# BMS_Rev3_logic.net
KiCad netlist of a schematic drawn in EAGLE
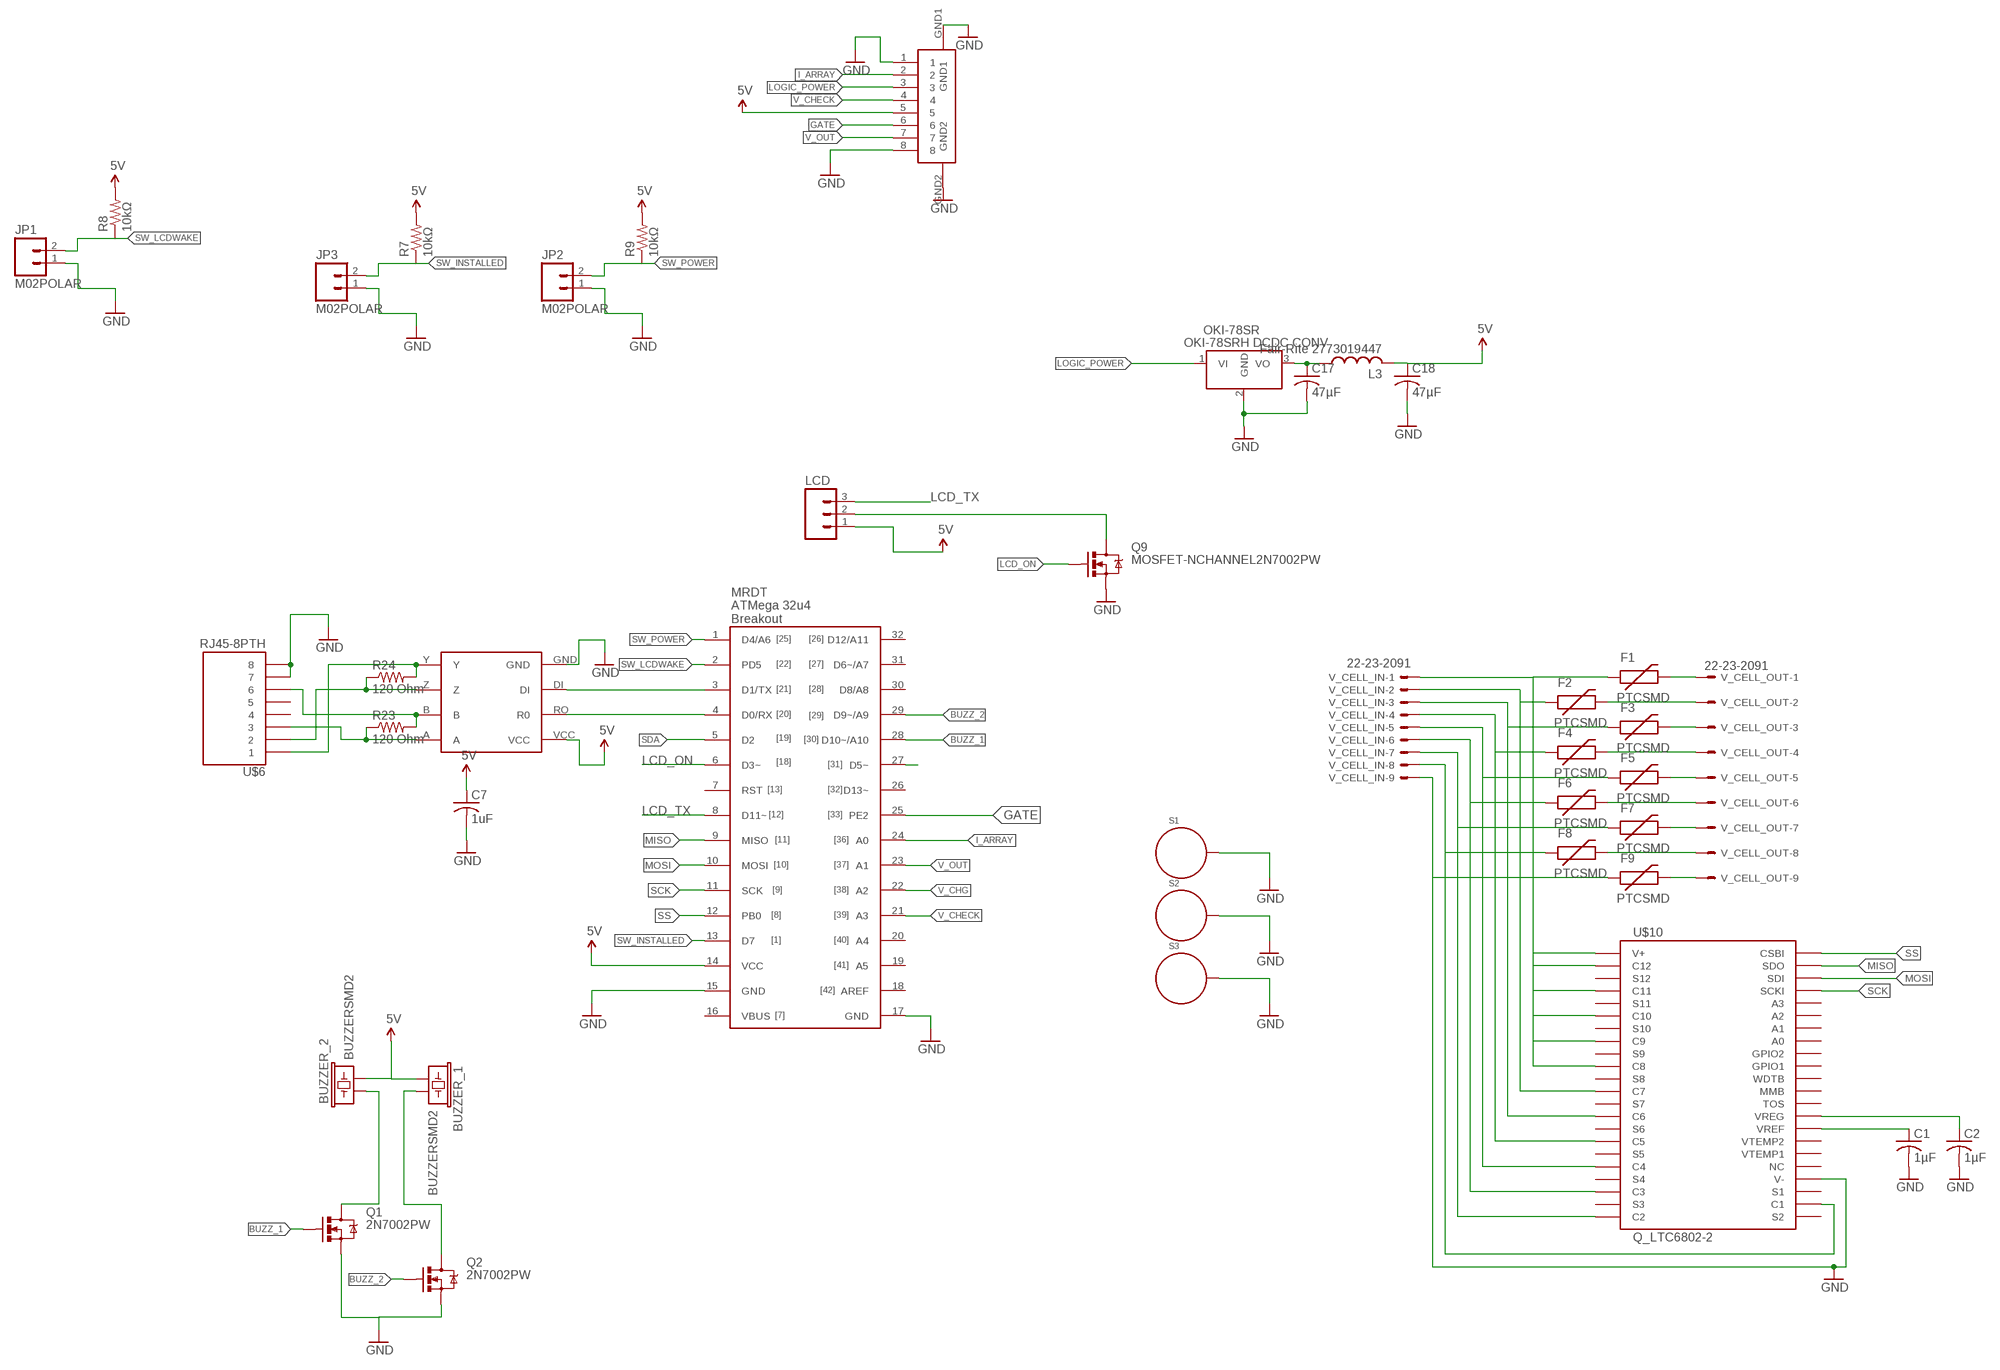
[diagram p0: schematic, sheet 1]

(export (version "E")
  (design (tool "Eeschema 10.0.6"))
  (components
    (comp (ref "BUZZER_1")
      (value "BUZZERSMD2")
      (footprint "eagle-import:BUZZER-CCV")
      (libsource (lib "eagle-import") (part "BUZZERSMD2"))
    )
    (comp (ref "BUZZER_2")
      (value "BUZZERSMD2")
      (footprint "eagle-import:BUZZER-CCV")
      (libsource (lib "eagle-import") (part "BUZZERSMD2"))
    )
    (comp (ref "C1")
      (value "1µF")
      (footprint "eagle-import:C1206")
      (libsource (lib "eagle-import") (part "C-USC1206"))
    )
    (comp (ref "C2")
      (value "1µF")
      (footprint "eagle-import:C1206")
      (libsource (lib "eagle-import") (part "C-USC1206"))
    )
    (comp (ref "C7")
      (value "1uF")
      (footprint "eagle-import:C1206")
      (libsource (lib "eagle-import") (part "C-USC1206"))
    )
    (comp (ref "C17")
      (value "47µF")
      (footprint "eagle-import:C1206")
      (libsource (lib "eagle-import") (part "C-USC1206"))
    )
    (comp (ref "C18")
      (value "47µF")
      (footprint "eagle-import:C1206")
      (libsource (lib "eagle-import") (part "C-USC1206"))
    )
    (comp (ref "F1")
      (value "PTCSMD")
      (footprint "eagle-import:PTC-1206")
      (libsource (lib "eagle-import") (part "PTCSMD"))
    )
    (comp (ref "F2")
      (value "PTCSMD")
      (footprint "eagle-import:PTC-1206")
      (libsource (lib "eagle-import") (part "PTCSMD"))
    )
    (comp (ref "F3")
      (value "PTCSMD")
      (footprint "eagle-import:PTC-1206")
      (libsource (lib "eagle-import") (part "PTCSMD"))
    )
    (comp (ref "F4")
      (value "PTCSMD")
      (footprint "eagle-import:PTC-1206")
      (libsource (lib "eagle-import") (part "PTCSMD"))
    )
    (comp (ref "F5")
      (value "PTCSMD")
      (footprint "eagle-import:PTC-1206")
      (libsource (lib "eagle-import") (part "PTCSMD"))
    )
    (comp (ref "F6")
      (value "PTCSMD")
      (footprint "eagle-import:PTC-1206")
      (libsource (lib "eagle-import") (part "PTCSMD"))
    )
    (comp (ref "F7")
      (value "PTCSMD")
      (footprint "eagle-import:PTC-1206")
      (libsource (lib "eagle-import") (part "PTCSMD"))
    )
    (comp (ref "F8")
      (value "PTCSMD")
      (footprint "eagle-import:PTC-1206")
      (libsource (lib "eagle-import") (part "PTCSMD"))
    )
    (comp (ref "F9")
      (value "PTCSMD")
      (footprint "eagle-import:PTC-1206")
      (libsource (lib "eagle-import") (part "PTCSMD"))
    )
    (comp (ref "JP1")
      (value "M02POLAR")
      (footprint "eagle-import:MOLEX-1X2")
      (libsource (lib "eagle-import") (part "M02POLAR"))
    )
    (comp (ref "JP2")
      (value "M02POLAR")
      (footprint "eagle-import:MOLEX-1X2")
      (libsource (lib "eagle-import") (part "M02POLAR"))
    )
    (comp (ref "JP3")
      (value "M02POLAR")
      (footprint "eagle-import:MOLEX-1X2")
      (libsource (lib "eagle-import") (part "M02POLAR"))
    )
    (comp (ref "L3")
      (value "Fair-Rite 2773019447")
      (footprint "eagle-import:L8530M")
      (libsource (lib "eagle-import") (part "L-USL8530M"))
    )
    (comp (ref "LCD")
      (value "M03POLAR")
      (footprint "eagle-import:MOLEX-1X3")
      (libsource (lib "eagle-import") (part "M03POLAR"))
    )
    (comp (ref "OKI-78SR")
      (value "Q_OKI-78SR")
      (footprint "eagle-import:OKI-78SRH")
      (libsource (lib "eagle-import") (part "Q_OKI-78SR"))
    )
    (comp (ref "Q1")
      (value "2N7002PW")
      (footprint "eagle-import:SOT323")
      (libsource (lib "eagle-import") (part "MOSFET-NCHANNEL2N7002PW"))
    )
    (comp (ref "Q2")
      (value "2N7002PW")
      (footprint "eagle-import:SOT323")
      (libsource (lib "eagle-import") (part "MOSFET-NCHANNEL2N7002PW"))
    )
    (comp (ref "Q9")
      (value "MOSFET-NCHANNEL2N7002PW")
      (footprint "eagle-import:SOT323")
      (libsource (lib "eagle-import") (part "MOSFET-NCHANNEL2N7002PW"))
    )
    (comp (ref "R7")
      (value "10kΩ")
      (footprint "eagle-import:R1206")
      (libsource (lib "eagle-import") (part "R-US_R1206"))
    )
    (comp (ref "R8")
      (value "10kΩ")
      (footprint "eagle-import:R1206")
      (libsource (lib "eagle-import") (part "R-US_R1206"))
    )
    (comp (ref "R9")
      (value "10kΩ")
      (footprint "eagle-import:R1206")
      (libsource (lib "eagle-import") (part "R-US_R1206"))
    )
    (comp (ref "R23")
      (value "120 Ohm")
      (footprint "eagle-import:1206")
      (libsource (lib "eagle-import") (part "RESISTOR1206"))
    )
    (comp (ref "R24")
      (value "120 Ohm")
      (footprint "eagle-import:1206")
      (libsource (lib "eagle-import") (part "RESISTOR1206"))
    )
    (comp (ref "S1")
      (value "STANDOFF_ELECTRICAL")
      (footprint "eagle-import:STANDOFF-ELECTRICAL")
      (libsource (lib "eagle-import") (part "STANDOFF_ELECTRICAL"))
    )
    (comp (ref "S2")
      (value "STANDOFF_ELECTRICAL")
      (footprint "eagle-import:STANDOFF-ELECTRICAL")
      (libsource (lib "eagle-import") (part "STANDOFF_ELECTRICAL"))
    )
    (comp (ref "S3")
      (value "STANDOFF_ELECTRICAL")
      (footprint "eagle-import:STANDOFF-ELECTRICAL")
      (libsource (lib "eagle-import") (part "STANDOFF_ELECTRICAL"))
    )
    (comp (ref "U$1")
      (value "8POS_LOGIC")
      (footprint "eagle-import:LOGIC_CONNECT")
      (libsource (lib "eagle-import") (part "8POS_LOGIC"))
    )
    (comp (ref "U$3")
      (value "32U4_BREAKOUT")
      (footprint "eagle-import:32U4_MCU_DIP")
      (libsource (lib "eagle-import") (part "32U4_BREAKOUT"))
    )
    (comp (ref "U$6")
      (value "RJ45-8PTH")
      (footprint "eagle-import:RJ45-8")
      (libsource (lib "eagle-import") (part "RJ45-8PTH"))
    )
    (comp (ref "U$9")
      (value "MAX3077")
      (footprint "eagle-import:MAX3070E")
      (libsource (lib "eagle-import") (part "MAX3077"))
    )
    (comp (ref "U$10")
      (value "Q_LTC6802-2")
      (footprint "eagle-import:SSOP44")
      (libsource (lib "eagle-import") (part "Q_LTC6802-2"))
    )
    (comp (ref "V_CELL_IN")
      (value "22-23-2091")
      (footprint "eagle-import:22-23-2091")
      (fields (field (name "MF") "MOLEX"))
      (libsource (lib "eagle-import") (part "22-23-2091"))
    )
    (comp (ref "V_CELL_OUT")
      (value "22-23-2091")
      (footprint "eagle-import:22-23-2091")
      (fields (field (name "MF") "MOLEX"))
      (libsource (lib "eagle-import") (part "22-23-2091"))
    )
  )
  (nets
    (net (code "1") (name "/LCD_TX") (class "Default")
      (node (ref "LCD") (pin "3") (pinfunction "3_3") (pintype "passive"))
      (node (ref "U$3") (pin "8") (pinfunction "D11~{}_8") (pintype "bidirectional"))
    )
    (net (code "2") (name "5V") (class "Default")
      (node (ref "BUZZER_1") (pin "+") (pinfunction "1_+") (pintype "passive"))
      (node (ref "BUZZER_2") (pin "-") (pinfunction "2_-") (pintype "passive"))
      (node (ref "C18") (pin "1") (pinfunction "1_1") (pintype "passive"))
      (node (ref "C7") (pin "1") (pinfunction "1_1") (pintype "passive"))
      (node (ref "L3") (pin "2") (pinfunction "2_2") (pintype "passive"))
      (node (ref "LCD") (pin "1") (pinfunction "1_1") (pintype "passive"))
      (node (ref "R7") (pin "2") (pinfunction "2_2") (pintype "passive"))
      (node (ref "R8") (pin "2") (pinfunction "2_2") (pintype "passive"))
      (node (ref "R9") (pin "2") (pinfunction "2_2") (pintype "passive"))
      (node (ref "U$1") (pin "5") (pinfunction "5_5") (pintype "bidirectional"))
      (node (ref "U$3") (pin "14") (pinfunction "VCC_14") (pintype "bidirectional"))
      (node (ref "U$9") (pin "VCC") (pinfunction "VCC_VCC") (pintype "bidirectional"))
    )
    (net (code "3") (name "BUZZ_1") (class "Default")
      (node (ref "Q1") (pin "1") (pinfunction "G_1") (pintype "passive"))
      (node (ref "U$3") (pin "28") (pinfunction "D10~{/A10}_28") (pintype "bidirectional"))
    )
    (net (code "4") (name "BUZZ_2") (class "Default")
      (node (ref "Q2") (pin "1") (pinfunction "G_1") (pintype "passive"))
      (node (ref "U$3") (pin "29") (pinfunction "D9~{/A9}_29") (pintype "bidirectional"))
    )
    (net (code "5") (name "GATE") (class "Default")
      (node (ref "U$1") (pin "6") (pinfunction "6_6") (pintype "bidirectional"))
      (node (ref "U$3") (pin "25") (pinfunction "PE2_25") (pintype "bidirectional"))
    )
    (net (code "6") (name "GND") (class "Default")
      (node (ref "C1") (pin "2") (pinfunction "2_2") (pintype "passive"))
      (node (ref "C17") (pin "2") (pinfunction "2_2") (pintype "passive"))
      (node (ref "C18") (pin "2") (pinfunction "2_2") (pintype "passive"))
      (node (ref "C2") (pin "2") (pinfunction "2_2") (pintype "passive"))
      (node (ref "C7") (pin "2") (pinfunction "2_2") (pintype "passive"))
      (node (ref "F9") (pin "1") (pinfunction "1_1") (pintype "bidirectional"))
      (node (ref "JP1") (pin "1") (pinfunction "1_1") (pintype "passive"))
      (node (ref "JP2") (pin "1") (pinfunction "1_1") (pintype "passive"))
      (node (ref "JP3") (pin "1") (pinfunction "1_1") (pintype "passive"))
      (node (ref "OKI-78SR") (pin "2") (pinfunction "GND_2") (pintype "bidirectional"))
      (node (ref "Q1") (pin "2") (pinfunction "S_2") (pintype "passive"))
      (node (ref "Q2") (pin "2") (pinfunction "S_2") (pintype "passive"))
      (node (ref "Q9") (pin "2") (pinfunction "S_2") (pintype "passive"))
      (node (ref "S1") (pin "P1") (pinfunction "P$1_P1") (pintype "bidirectional"))
      (node (ref "S2") (pin "P1") (pinfunction "P$1_P1") (pintype "bidirectional"))
      (node (ref "S3") (pin "P1") (pinfunction "P$1_P1") (pintype "bidirectional"))
      (node (ref "U$1") (pin "1") (pinfunction "1_1") (pintype "bidirectional"))
      (node (ref "U$1") (pin "8") (pinfunction "8_8") (pintype "bidirectional"))
      (node (ref "U$1") (pin "GND1") (pinfunction "GND1_GND1") (pintype "bidirectional"))
      (node (ref "U$1") (pin "GND2") (pinfunction "GND2_GND2") (pintype "bidirectional"))
      (node (ref "U$10") (pin "26") (pinfunction "V-_26") (pintype "bidirectional"))
      (node (ref "U$3") (pin "15") (pinfunction "GND_15") (pintype "bidirectional"))
      (node (ref "U$3") (pin "17") (pinfunction "GND_17") (pintype "bidirectional"))
      (node (ref "U$6") (pin "7") (pinfunction "7_7") (pintype "bidirectional"))
      (node (ref "U$6") (pin "8") (pinfunction "8_8") (pintype "bidirectional"))
      (node (ref "U$9") (pin "GND") (pinfunction "GND_GND") (pintype "bidirectional"))
      (node (ref "V_CELL_IN") (pin "9") (pinfunction "S_9") (pintype "passive"))
    )
    (net (code "7") (name "I_ARRAY") (class "Default")
      (node (ref "U$1") (pin "2") (pinfunction "2_2") (pintype "bidirectional"))
      (node (ref "U$3") (pin "24") (pinfunction "A0_24") (pintype "bidirectional"))
    )
    (net (code "8") (name "LCD_ON") (class "Default")
      (node (ref "Q9") (pin "1") (pinfunction "G_1") (pintype "passive"))
      (node (ref "U$3") (pin "6") (pinfunction "D3~{}_6") (pintype "bidirectional"))
    )
    (net (code "9") (name "LOGIC_POWER") (class "Default")
      (node (ref "OKI-78SR") (pin "1") (pinfunction "VI_1") (pintype "bidirectional"))
      (node (ref "U$1") (pin "3") (pinfunction "3_3") (pintype "bidirectional"))
    )
    (net (code "10") (name "MISO") (class "Default")
      (node (ref "U$10") (pin "43") (pinfunction "SDO_43") (pintype "bidirectional"))
      (node (ref "U$3") (pin "9") (pinfunction "MISO_9") (pintype "bidirectional"))
    )
    (net (code "11") (name "MOSI") (class "Default")
      (node (ref "U$10") (pin "42") (pinfunction "SDI_42") (pintype "bidirectional"))
      (node (ref "U$3") (pin "10") (pinfunction "MOSI_10") (pintype "bidirectional"))
    )
    (net (code "12") (name "Net-(BUZZER_1-2)") (class "Default")
      (node (ref "BUZZER_1") (pin "-") (pinfunction "2_-") (pintype "passive"))
      (node (ref "Q2") (pin "3") (pinfunction "D_3") (pintype "passive"))
    )
    (net (code "13") (name "Net-(BUZZER_2-1)") (class "Default")
      (node (ref "BUZZER_2") (pin "+") (pinfunction "1_+") (pintype "passive"))
      (node (ref "Q1") (pin "3") (pinfunction "D_3") (pintype "passive"))
    )
    (net (code "14") (name "Net-(OKI-78SR-VO)") (class "Default")
      (node (ref "C17") (pin "1") (pinfunction "1_1") (pintype "passive"))
      (node (ref "L3") (pin "1") (pinfunction "1_1") (pintype "passive"))
      (node (ref "OKI-78SR") (pin "3") (pinfunction "VO_3") (pintype "bidirectional"))
    )
    (net (code "15") (name "Net-(Q9-D)") (class "Default")
      (node (ref "LCD") (pin "2") (pinfunction "2_2") (pintype "passive"))
      (node (ref "Q9") (pin "3") (pinfunction "D_3") (pintype "passive"))
    )
    (net (code "16") (name "Net-(R23-Pad1)") (class "Default")
      (node (ref "R23") (pin "1") (pinfunction "1_1") (pintype "passive"))
      (node (ref "U$6") (pin "3") (pinfunction "3_3") (pintype "bidirectional"))
      (node (ref "U$9") (pin "A") (pinfunction "A_A") (pintype "bidirectional"))
    )
    (net (code "17") (name "Net-(R23-Pad2)") (class "Default")
      (node (ref "R23") (pin "2") (pinfunction "2_2") (pintype "passive"))
      (node (ref "U$6") (pin "6") (pinfunction "6_6") (pintype "bidirectional"))
      (node (ref "U$9") (pin "B") (pinfunction "B_B") (pintype "bidirectional"))
    )
    (net (code "18") (name "Net-(R24-Pad1)") (class "Default")
      (node (ref "R24") (pin "1") (pinfunction "1_1") (pintype "passive"))
      (node (ref "U$6") (pin "2") (pinfunction "2_2") (pintype "bidirectional"))
      (node (ref "U$9") (pin "Z") (pinfunction "Z_Z") (pintype "bidirectional"))
    )
    (net (code "19") (name "Net-(R24-Pad2)") (class "Default")
      (node (ref "R24") (pin "2") (pinfunction "2_2") (pintype "passive"))
      (node (ref "U$6") (pin "1") (pinfunction "1_1") (pintype "bidirectional"))
      (node (ref "U$9") (pin "Y") (pinfunction "Y_Y") (pintype "bidirectional"))
    )
    (net (code "20") (name "Net-(U$3-D0{slash}RX)") (class "Default")
      (node (ref "U$3") (pin "4") (pinfunction "D0/RX_4") (pintype "bidirectional"))
      (node (ref "U$9") (pin "RO") (pinfunction "R0_RO") (pintype "bidirectional"))
    )
    (net (code "21") (name "Net-(U$3-D1{slash}TX)") (class "Default")
      (node (ref "U$3") (pin "3") (pinfunction "D1/TX_3") (pintype "bidirectional"))
      (node (ref "U$9") (pin "DI") (pinfunction "DI_DI") (pintype "bidirectional"))
    )
    (net (code "22") (name "Net-(U$10-C1)") (class "Default")
      (node (ref "F8") (pin "1") (pinfunction "1_1") (pintype "bidirectional"))
      (node (ref "U$10") (pin "24") (pinfunction "C1_24") (pintype "bidirectional"))
      (node (ref "V_CELL_IN") (pin "8") (pinfunction "S_8") (pintype "passive"))
    )
    (net (code "23") (name "Net-(U$10-C2)") (class "Default")
      (node (ref "F7") (pin "1") (pinfunction "1_1") (pintype "bidirectional"))
      (node (ref "U$10") (pin "22") (pinfunction "C2_22") (pintype "bidirectional"))
      (node (ref "V_CELL_IN") (pin "7") (pinfunction "S_7") (pintype "passive"))
    )
    (net (code "24") (name "Net-(U$10-C3)") (class "Default")
      (node (ref "F6") (pin "1") (pinfunction "1_1") (pintype "bidirectional"))
      (node (ref "U$10") (pin "20") (pinfunction "C3_20") (pintype "bidirectional"))
      (node (ref "V_CELL_IN") (pin "6") (pinfunction "S_6") (pintype "passive"))
    )
    (net (code "25") (name "Net-(U$10-C4)") (class "Default")
      (node (ref "F5") (pin "1") (pinfunction "1_1") (pintype "bidirectional"))
      (node (ref "U$10") (pin "18") (pinfunction "C4_18") (pintype "bidirectional"))
      (node (ref "V_CELL_IN") (pin "5") (pinfunction "S_5") (pintype "passive"))
    )
    (net (code "26") (name "Net-(U$10-C5)") (class "Default")
      (node (ref "F4") (pin "1") (pinfunction "1_1") (pintype "bidirectional"))
      (node (ref "U$10") (pin "16") (pinfunction "C5_16") (pintype "bidirectional"))
      (node (ref "V_CELL_IN") (pin "4") (pinfunction "S_4") (pintype "passive"))
    )
    (net (code "27") (name "Net-(U$10-C6)") (class "Default")
      (node (ref "F3") (pin "1") (pinfunction "1_1") (pintype "bidirectional"))
      (node (ref "U$10") (pin "14") (pinfunction "C6_14") (pintype "bidirectional"))
      (node (ref "V_CELL_IN") (pin "3") (pinfunction "S_3") (pintype "passive"))
    )
    (net (code "28") (name "Net-(U$10-C7)") (class "Default")
      (node (ref "F2") (pin "1") (pinfunction "1_1") (pintype "bidirectional"))
      (node (ref "U$10") (pin "12") (pinfunction "C7_12") (pintype "bidirectional"))
      (node (ref "V_CELL_IN") (pin "2") (pinfunction "S_2") (pintype "passive"))
    )
    (net (code "29") (name "Net-(U$10-C10)") (class "Default")
      (node (ref "F1") (pin "1") (pinfunction "1_1") (pintype "bidirectional"))
      (node (ref "U$10") (pin "1") (pinfunction "V+_1") (pintype "bidirectional"))
      (node (ref "U$10") (pin "10") (pinfunction "C8_10") (pintype "bidirectional"))
      (node (ref "U$10") (pin "2") (pinfunction "C12_2") (pintype "bidirectional"))
      (node (ref "U$10") (pin "4") (pinfunction "C11_4") (pintype "bidirectional"))
      (node (ref "U$10") (pin "6") (pinfunction "C10_6") (pintype "bidirectional"))
      (node (ref "U$10") (pin "8") (pinfunction "C9_8") (pintype "bidirectional"))
      (node (ref "V_CELL_IN") (pin "1") (pinfunction "S_1") (pintype "passive"))
    )
    (net (code "30") (name "Net-(U$10-VREF)") (class "Default")
      (node (ref "C1") (pin "1") (pinfunction "1_1") (pintype "passive"))
      (node (ref "U$10") (pin "30") (pinfunction "VREF_30") (pintype "bidirectional"))
    )
    (net (code "31") (name "Net-(U$10-VREG)") (class "Default")
      (node (ref "C2") (pin "1") (pinfunction "1_1") (pintype "passive"))
      (node (ref "U$10") (pin "31") (pinfunction "VREG_31") (pintype "bidirectional"))
    )
    (net (code "32") (name "Net-(V_CELL_OUTA-S)") (class "Default")
      (node (ref "F1") (pin "2") (pinfunction "2_2") (pintype "bidirectional"))
      (node (ref "V_CELL_OUT") (pin "1") (pinfunction "S_1") (pintype "passive"))
    )
    (net (code "33") (name "Net-(V_CELL_OUTB-S)") (class "Default")
      (node (ref "F2") (pin "2") (pinfunction "2_2") (pintype "bidirectional"))
      (node (ref "V_CELL_OUT") (pin "2") (pinfunction "S_2") (pintype "passive"))
    )
    (net (code "34") (name "Net-(V_CELL_OUTC-S)") (class "Default")
      (node (ref "F3") (pin "2") (pinfunction "2_2") (pintype "bidirectional"))
      (node (ref "V_CELL_OUT") (pin "3") (pinfunction "S_3") (pintype "passive"))
    )
    (net (code "35") (name "Net-(V_CELL_OUTD-S)") (class "Default")
      (node (ref "F4") (pin "2") (pinfunction "2_2") (pintype "bidirectional"))
      (node (ref "V_CELL_OUT") (pin "4") (pinfunction "S_4") (pintype "passive"))
    )
    (net (code "36") (name "Net-(V_CELL_OUTE-S)") (class "Default")
      (node (ref "F5") (pin "2") (pinfunction "2_2") (pintype "bidirectional"))
      (node (ref "V_CELL_OUT") (pin "5") (pinfunction "S_5") (pintype "passive"))
    )
    (net (code "37") (name "Net-(V_CELL_OUTF-S)") (class "Default")
      (node (ref "F6") (pin "2") (pinfunction "2_2") (pintype "bidirectional"))
      (node (ref "V_CELL_OUT") (pin "6") (pinfunction "S_6") (pintype "passive"))
    )
    (net (code "38") (name "Net-(V_CELL_OUTG-S)") (class "Default")
      (node (ref "F7") (pin "2") (pinfunction "2_2") (pintype "bidirectional"))
      (node (ref "V_CELL_OUT") (pin "7") (pinfunction "S_7") (pintype "passive"))
    )
    (net (code "39") (name "Net-(V_CELL_OUTH-S)") (class "Default")
      (node (ref "F8") (pin "2") (pinfunction "2_2") (pintype "bidirectional"))
      (node (ref "V_CELL_OUT") (pin "8") (pinfunction "S_8") (pintype "passive"))
    )
    (net (code "40") (name "Net-(V_CELL_OUTI-S)") (class "Default")
      (node (ref "F9") (pin "2") (pinfunction "2_2") (pintype "bidirectional"))
      (node (ref "V_CELL_OUT") (pin "9") (pinfunction "S_9") (pintype "passive"))
    )
    (net (code "41") (name "SCK") (class "Default")
      (node (ref "U$10") (pin "41") (pinfunction "SCKI_41") (pintype "bidirectional"))
      (node (ref "U$3") (pin "11") (pinfunction "SCK_11") (pintype "bidirectional"))
    )
    (net (code "42") (name "SDA") (class "Default")
      (node (ref "U$3") (pin "5") (pinfunction "D2_5") (pintype "bidirectional"))
    )
    (net (code "43") (name "SS") (class "Default")
      (node (ref "U$10") (pin "44") (pinfunction "CSBI_44") (pintype "bidirectional"))
      (node (ref "U$3") (pin "12") (pinfunction "PB0_12") (pintype "bidirectional"))
    )
    (net (code "44") (name "SW_INSTALLED") (class "Default")
      (node (ref "JP3") (pin "2") (pinfunction "2_2") (pintype "passive"))
      (node (ref "R7") (pin "1") (pinfunction "1_1") (pintype "passive"))
      (node (ref "U$3") (pin "13") (pinfunction "D7_13") (pintype "bidirectional"))
    )
    (net (code "45") (name "SW_LCDWAKE") (class "Default")
      (node (ref "JP1") (pin "2") (pinfunction "2_2") (pintype "passive"))
      (node (ref "R8") (pin "1") (pinfunction "1_1") (pintype "passive"))
      (node (ref "U$3") (pin "2") (pinfunction "PD5_2") (pintype "bidirectional"))
    )
    (net (code "46") (name "SW_POWER") (class "Default")
      (node (ref "JP2") (pin "2") (pinfunction "2_2") (pintype "passive"))
      (node (ref "R9") (pin "1") (pinfunction "1_1") (pintype "passive"))
      (node (ref "U$3") (pin "1") (pinfunction "D4/A6_1") (pintype "bidirectional"))
    )
    (net (code "47") (name "V_CHECK") (class "Default")
      (node (ref "U$1") (pin "4") (pinfunction "4_4") (pintype "bidirectional"))
      (node (ref "U$3") (pin "21") (pinfunction "A3_21") (pintype "bidirectional"))
    )
    (net (code "48") (name "V_CHG") (class "Default")
      (node (ref "U$3") (pin "22") (pinfunction "A2_22") (pintype "bidirectional"))
    )
    (net (code "49") (name "V_OUT") (class "Default")
      (node (ref "U$1") (pin "7") (pinfunction "7_7") (pintype "bidirectional"))
      (node (ref "U$3") (pin "23") (pinfunction "A1_23") (pintype "bidirectional"))
    )
    (net (code "50") (name "unconnected-(U$3-A4-Pad20)") (class "Default")
      (node (ref "U$3") (pin "20") (pinfunction "A4_20") (pintype "bidirectional"))
    )
    (net (code "51") (name "unconnected-(U$3-A5-Pad19)") (class "Default")
      (node (ref "U$3") (pin "19") (pinfunction "A5_19") (pintype "bidirectional"))
    )
    (net (code "52") (name "unconnected-(U$3-AREF-Pad18)") (class "Default")
      (node (ref "U$3") (pin "18") (pinfunction "AREF_18") (pintype "bidirectional"))
    )
    (net (code "53") (name "unconnected-(U$3-D5~{}-Pad27)") (class "Default")
      (node (ref "U$3") (pin "27") (pinfunction "D5~{}_27") (pintype "bidirectional"))
    )
    (net (code "54") (name "unconnected-(U$3-D6~{{slash}A7}-Pad31)") (class "Default")
      (node (ref "U$3") (pin "31") (pinfunction "D6~{/A7}_31") (pintype "bidirectional"))
    )
    (net (code "55") (name "unconnected-(U$3-D8{slash}A8-Pad30)") (class "Default")
      (node (ref "U$3") (pin "30") (pinfunction "D8/A8_30") (pintype "bidirectional"))
    )
    (net (code "56") (name "unconnected-(U$3-D12{slash}A11-Pad32)") (class "Default")
      (node (ref "U$3") (pin "32") (pinfunction "D12/A11_32") (pintype "bidirectional"))
    )
    (net (code "57") (name "unconnected-(U$3-D13~{}-Pad26)") (class "Default")
      (node (ref "U$3") (pin "26") (pinfunction "D13~{}_26") (pintype "bidirectional"))
    )
    (net (code "58") (name "unconnected-(U$3-RST-Pad7)") (class "Default")
      (node (ref "U$3") (pin "7") (pinfunction "RST_7") (pintype "bidirectional"))
    )
    (net (code "59") (name "unconnected-(U$3-VBUS-Pad16)") (class "Default")
      (node (ref "U$3") (pin "16") (pinfunction "VBUS_16") (pintype "bidirectional"))
    )
    (net (code "60") (name "unconnected-(U$6-Pad4)") (class "Default")
      (node (ref "U$6") (pin "4") (pinfunction "4_4") (pintype "bidirectional"))
    )
    (net (code "61") (name "unconnected-(U$6-Pad5)") (class "Default")
      (node (ref "U$6") (pin "5") (pinfunction "5_5") (pintype "bidirectional"))
    )
    (net (code "62") (name "unconnected-(U$10-A0-Pad37)") (class "Default")
      (node (ref "U$10") (pin "37") (pinfunction "A0_37") (pintype "bidirectional"))
    )
    (net (code "63") (name "unconnected-(U$10-A1-Pad38)") (class "Default")
      (node (ref "U$10") (pin "38") (pinfunction "A1_38") (pintype "bidirectional"))
    )
    (net (code "64") (name "unconnected-(U$10-A2-Pad39)") (class "Default")
      (node (ref "U$10") (pin "39") (pinfunction "A2_39") (pintype "bidirectional"))
    )
    (net (code "65") (name "unconnected-(U$10-A3-Pad40)") (class "Default")
      (node (ref "U$10") (pin "40") (pinfunction "A3_40") (pintype "bidirectional"))
    )
    (net (code "66") (name "unconnected-(U$10-GPIO1-Pad35)") (class "Default")
      (node (ref "U$10") (pin "35") (pinfunction "GPIO1_35") (pintype "bidirectional"))
    )
    (net (code "67") (name "unconnected-(U$10-GPIO2-Pad36)") (class "Default")
      (node (ref "U$10") (pin "36") (pinfunction "GPIO2_36") (pintype "bidirectional"))
    )
    (net (code "68") (name "unconnected-(U$10-MMB-Pad33)") (class "Default")
      (node (ref "U$10") (pin "33") (pinfunction "MMB_33") (pintype "bidirectional"))
    )
    (net (code "69") (name "unconnected-(U$10-NC-Pad27)") (class "Default")
      (node (ref "U$10") (pin "27") (pinfunction "NC_27") (pintype "bidirectional"))
    )
    (net (code "70") (name "unconnected-(U$10-S1-Pad25)") (class "Default")
      (node (ref "U$10") (pin "25") (pinfunction "S1_25") (pintype "bidirectional"))
    )
    (net (code "71") (name "unconnected-(U$10-S2-Pad23)") (class "Default")
      (node (ref "U$10") (pin "23") (pinfunction "S2_23") (pintype "bidirectional"))
    )
    (net (code "72") (name "unconnected-(U$10-S3-Pad21)") (class "Default")
      (node (ref "U$10") (pin "21") (pinfunction "S3_21") (pintype "bidirectional"))
    )
    (net (code "73") (name "unconnected-(U$10-S4-Pad19)") (class "Default")
      (node (ref "U$10") (pin "19") (pinfunction "S4_19") (pintype "bidirectional"))
    )
    (net (code "74") (name "unconnected-(U$10-S5-Pad17)") (class "Default")
      (node (ref "U$10") (pin "17") (pinfunction "S5_17") (pintype "bidirectional"))
    )
    (net (code "75") (name "unconnected-(U$10-S6-Pad15)") (class "Default")
      (node (ref "U$10") (pin "15") (pinfunction "S6_15") (pintype "bidirectional"))
    )
    (net (code "76") (name "unconnected-(U$10-S7-Pad13)") (class "Default")
      (node (ref "U$10") (pin "13") (pinfunction "S7_13") (pintype "bidirectional"))
    )
    (net (code "77") (name "unconnected-(U$10-S8-Pad11)") (class "Default")
      (node (ref "U$10") (pin "11") (pinfunction "S8_11") (pintype "bidirectional"))
    )
    (net (code "78") (name "unconnected-(U$10-S9-Pad9)") (class "Default")
      (node (ref "U$10") (pin "9") (pinfunction "S9_9") (pintype "bidirectional"))
    )
    (net (code "79") (name "unconnected-(U$10-S10-Pad7)") (class "Default")
      (node (ref "U$10") (pin "7") (pinfunction "S10_7") (pintype "bidirectional"))
    )
    (net (code "80") (name "unconnected-(U$10-S11-Pad5)") (class "Default")
      (node (ref "U$10") (pin "5") (pinfunction "S11_5") (pintype "bidirectional"))
    )
    (net (code "81") (name "unconnected-(U$10-S12-Pad3)") (class "Default")
      (node (ref "U$10") (pin "3") (pinfunction "S12_3") (pintype "bidirectional"))
    )
    (net (code "82") (name "unconnected-(U$10-TOS-Pad32)") (class "Default")
      (node (ref "U$10") (pin "32") (pinfunction "TOS_32") (pintype "bidirectional"))
    )
    (net (code "83") (name "unconnected-(U$10-VTEMP1-Pad28)") (class "Default")
      (node (ref "U$10") (pin "28") (pinfunction "VTEMP1_28") (pintype "bidirectional"))
    )
    (net (code "84") (name "unconnected-(U$10-VTEMP2-Pad29)") (class "Default")
      (node (ref "U$10") (pin "29") (pinfunction "VTEMP2_29") (pintype "bidirectional"))
    )
    (net (code "85") (name "unconnected-(U$10-WDTB-Pad34)") (class "Default")
      (node (ref "U$10") (pin "34") (pinfunction "WDTB_34") (pintype "bidirectional"))
    )
  )
)
